# SCH_Pico-Greenhouse-PCB_2026-05-22.net
KiCad netlist of a schematic drawn in EasyEDA
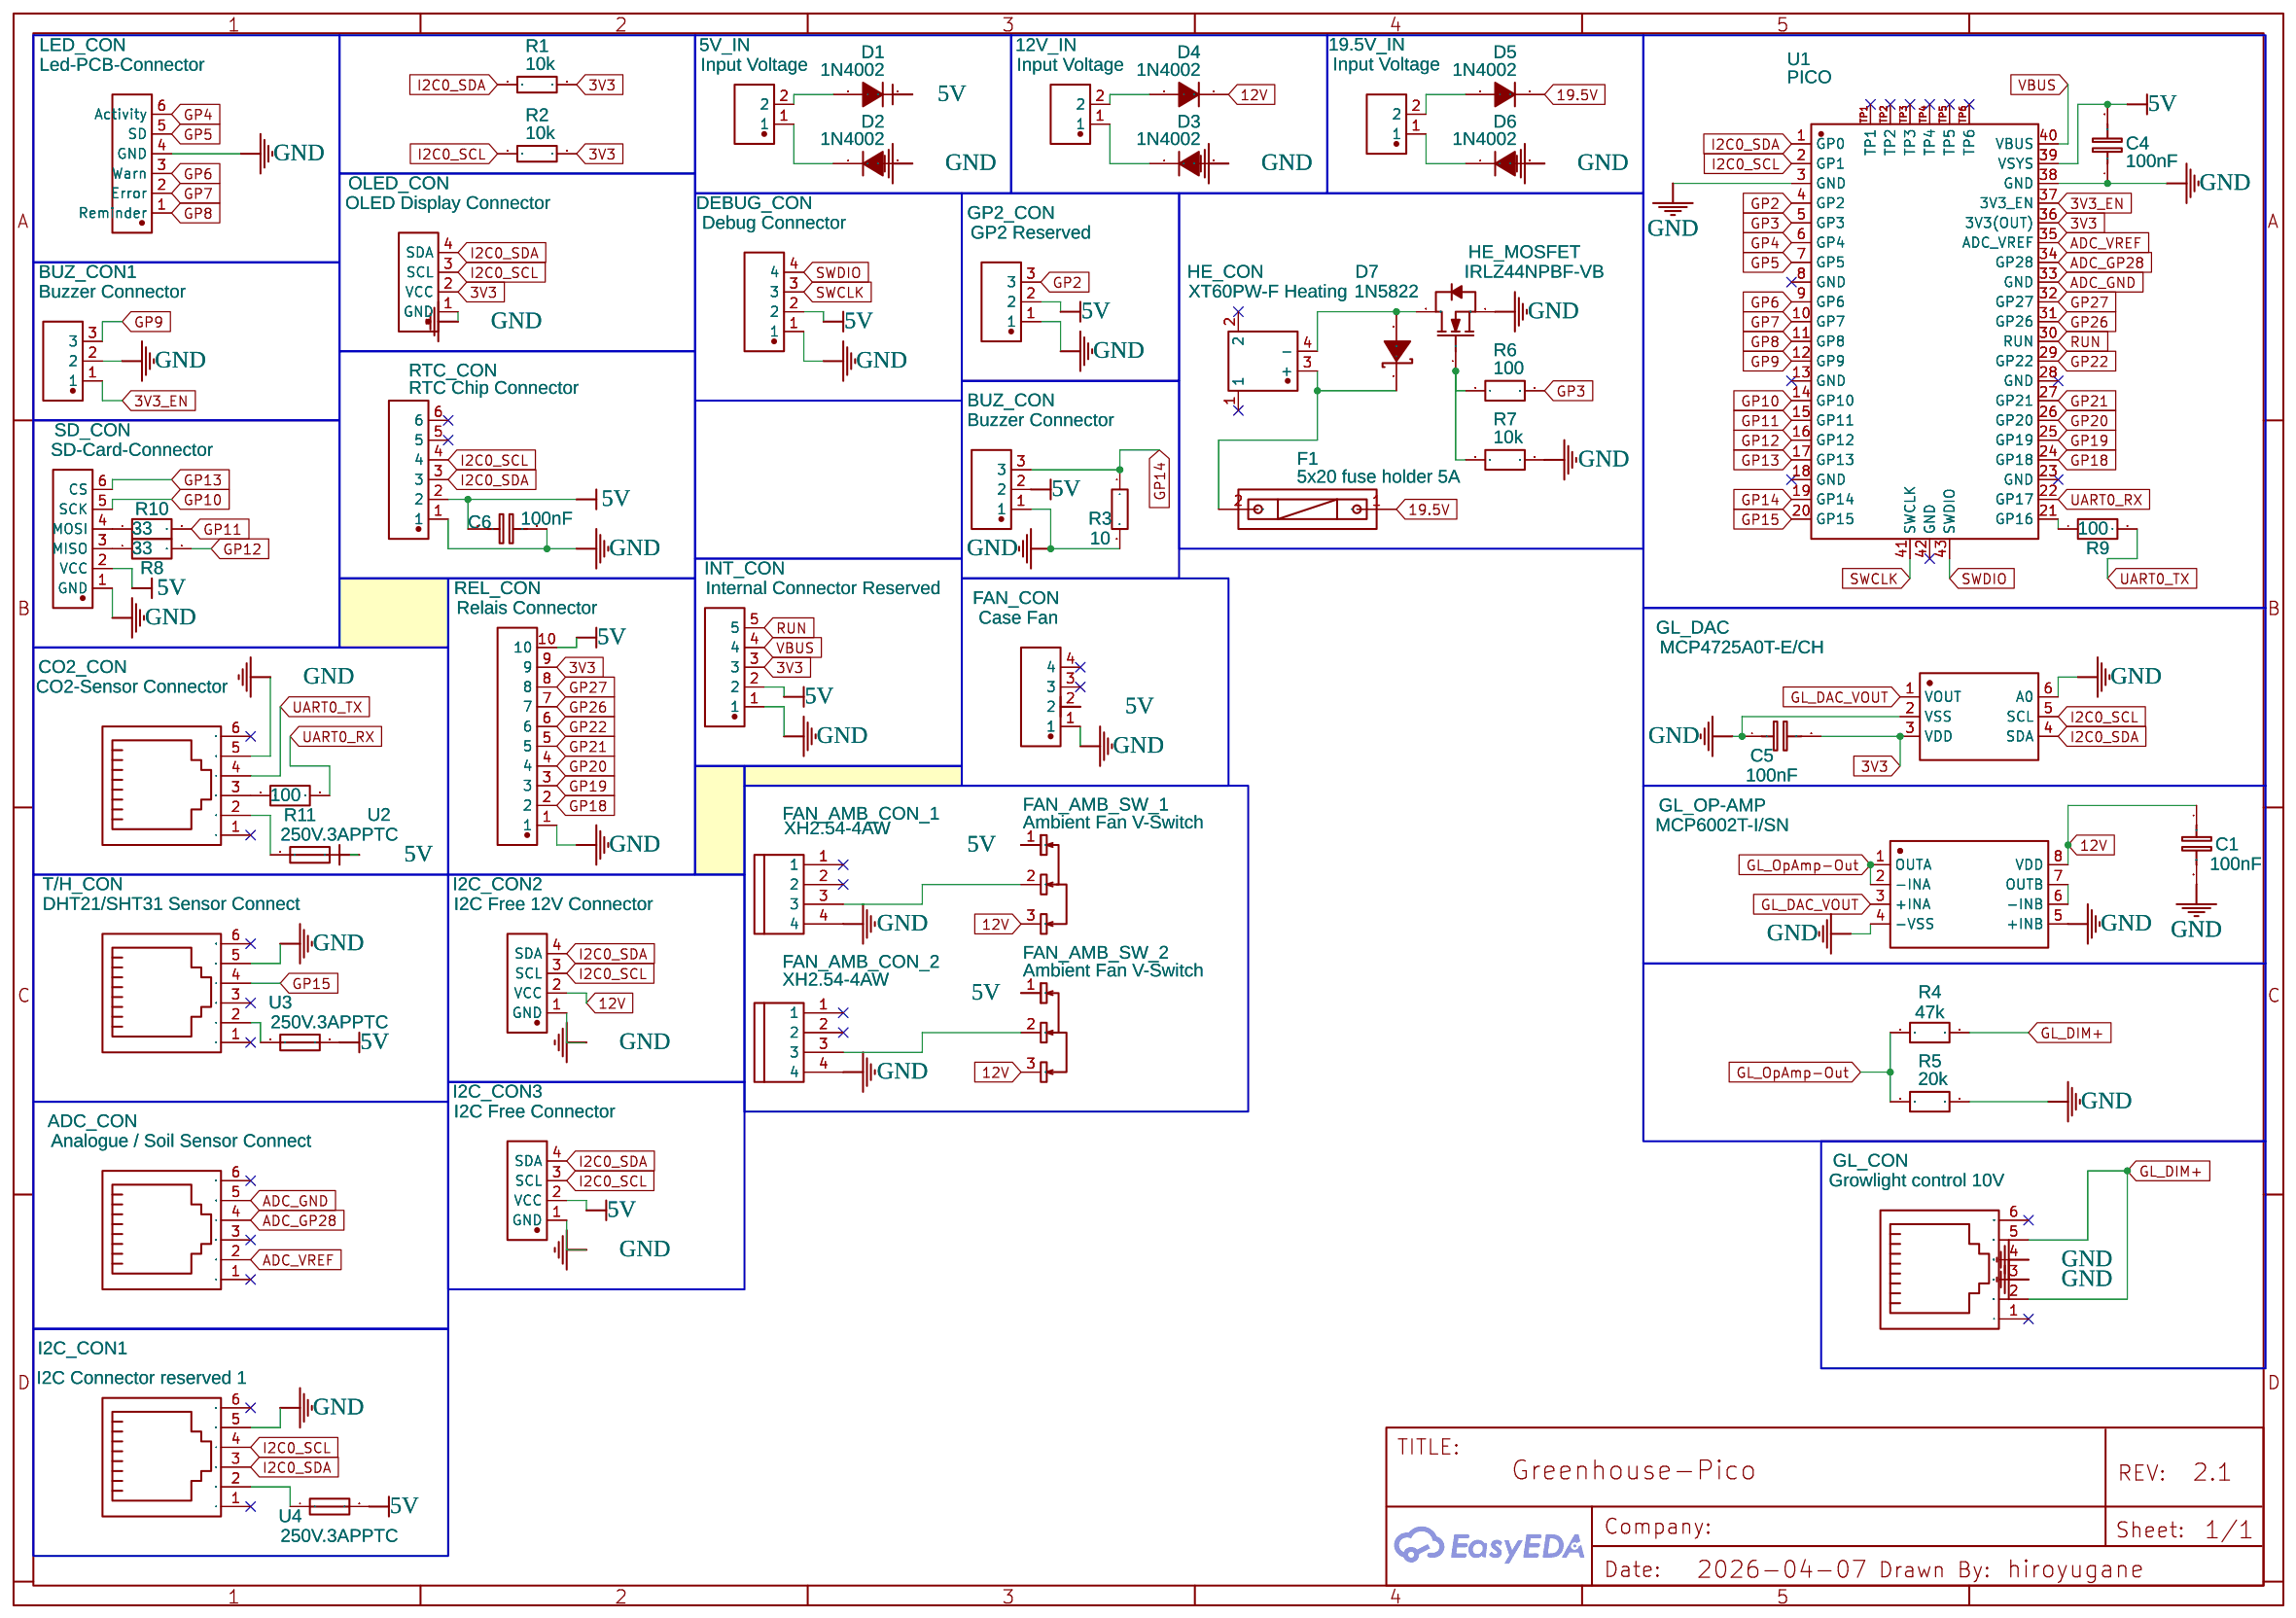
[diagram p0: schematic sheet]

(export (version "E")
  (design (tool "Eeschema 10.0.6"))
  (components
    (comp (ref "5V_IN")
      (value "Input Voltage")
      (fields (field (name "Manufacturer Part") "B2B-XH-A-BK(LF)(SN)") (field (name "Manufacturer") "JST"))
      (libsource (lib "") (part "B2B-XH-A-BK(LF)(SN)_1"))
    )
    (comp (ref "12V_IN")
      (value "Input Voltage")
      (fields (field (name "Manufacturer Part") "B2B-XH-A-BK(LF)(SN)") (field (name "Manufacturer") "JST"))
      (libsource (lib "") (part "B2B-XH-A-BK(LF)(SN)"))
    )
    (comp (ref "19.5V_IN")
      (value "Input Voltage")
      (fields
        (field (name "Manufacturer Part") "1935161")
        (field (name "Manufacturer") "Phoenix Contact(菲尼克斯)")
      )
      (libsource (lib "") (part "1935161"))
    )
    (comp (ref "ADC_CON")
      (value "Analogue / Soil Sensor Connect")
      (fields (field (name "Manufacturer Part") "955012661") (field (name "Manufacturer") "MOLEX"))
      (libsource (lib "") (part "95501-2661"))
    )
    (comp (ref "BUZ_CON")
      (value "Buzzer Connector")
      (fields (field (name "Manufacturer Part") "B3B-XH-A-BK(LF)(SN)") (field (name "Manufacturer") "JST"))
      (libsource (lib "") (part "B3B-XH-A-BK(LF)(SN)_1"))
    )
    (comp (ref "BUZ_CON1")
      (value "Buzzer Connector")
      (fields (field (name "Manufacturer Part") "B3B-XH-A-BK(LF)(SN)") (field (name "Manufacturer") "JST"))
      (libsource (lib "") (part "B3B-XH-A-BK(LF)(SN)_1"))
    )
    (comp (ref "C1") (value "100nF") (libsource (lib "") (part "C_0603_EU_3")))
    (comp (ref "C4") (value "100nF") (libsource (lib "") (part "C_0603_EU_1")))
    (comp (ref "C5") (value "100nF") (libsource (lib "") (part "C_0603_EU")))
    (comp (ref "C6") (value "100nF") (libsource (lib "") (part "C_0603_EU_2")))
    (comp (ref "CO2_CON")
      (value "CO2-Sensor Connector")
      (fields (field (name "Manufacturer Part") "955012661") (field (name "Manufacturer") "MOLEX"))
      (libsource (lib "") (part "95501-2661_4"))
    )
    (comp (ref "D1")
      (value "1N4002")
      (fields (field (name "Manufacturer Part") "1N4002-E3/54") (field (name "Manufacturer") "VISHAY(威世)"))
      (libsource (lib "") (part "1N4002-E3/54"))
    )
    (comp (ref "D2")
      (value "1N4002")
      (fields (field (name "Manufacturer Part") "1N4002-E3/54") (field (name "Manufacturer") "VISHAY(威世)"))
      (libsource (lib "") (part "1N4002-E3/54_1"))
    )
    (comp (ref "D3")
      (value "1N4002")
      (fields (field (name "Manufacturer Part") "1N4002-E3/54") (field (name "Manufacturer") "VISHAY(威世)"))
      (libsource (lib "") (part "1N4002-E3/54_1"))
    )
    (comp (ref "D4")
      (value "1N4002")
      (fields (field (name "Manufacturer Part") "1N4002-E3/54") (field (name "Manufacturer") "VISHAY(威世)"))
      (libsource (lib "") (part "1N4002-E3/54"))
    )
    (comp (ref "D5")
      (value "1N4002")
      (fields (field (name "Manufacturer Part") "1N4002-E3/54") (field (name "Manufacturer") "VISHAY(威世)"))
      (libsource (lib "") (part "1N4002-E3/54"))
    )
    (comp (ref "D6")
      (value "1N4002")
      (fields (field (name "Manufacturer Part") "1N4002-E3/54") (field (name "Manufacturer") "VISHAY(威世)"))
      (libsource (lib "") (part "1N4002-E3/54_1"))
    )
    (comp (ref "D7")
      (value "1N5822")
      (fields (field (name "Manufacturer") "MDD(辰达半导体)"))
      (libsource (lib "") (part "1N5822"))
    )
    (comp (ref "DEBUG_CON")
      (value "Debug Connector")
      (fields (field (name "Manufacturer Part") "B4B-XH-A-R(LF)(SN)") (field (name "Manufacturer") "JST"))
      (libsource (lib "") (part "B4B-XH-A-R(LF)(SN)_3"))
    )
    (comp (ref "F1")
      (value "5x20 fuse holder 5A")
      (fields
        (field (name "Manufacturer Part") "5x20 BLX-A型 保险丝支架 XC-7")
        (field (name "Manufacturer") "xcfuse(旭程)")
      )
      (libsource (lib "") (part "5x20 BLX-Atype Fuse holder XC-7"))
    )
    (comp (ref "FAN_AMB_CON_1")
      (value "XH2.54-4AW")
      (fields (field (name "Manufacturer Part") "XH-4AW") (field (name "Manufacturer") "BOOMELE(博穆精密)"))
      (libsource (lib "") (part "XH2.54-4AW"))
    )
    (comp (ref "FAN_AMB_CON_2")
      (value "XH2.54-4AW")
      (fields (field (name "Manufacturer Part") "XH-4AW") (field (name "Manufacturer") "BOOMELE(博穆精密)"))
      (libsource (lib "") (part "XH2.54-4AW"))
    )
    (comp (ref "FAN_AMB_SW_1")
      (value "Ambient Fan V-Switch")
      (fields
        (field (name "Manufacturer Part") "MST-12D18G4 SPDT Slide Switch")
        (field (name "Manufacturer") "SHOU HAN(首韩)")
      )
      (libsource (lib "") (part "MST-12D18G4 SPDT SLIDE SWITCH"))
    )
    (comp (ref "FAN_AMB_SW_2")
      (value "Ambient Fan V-Switch")
      (fields
        (field (name "Manufacturer Part") "MST-12D18G4 SPDT Slide Switch")
        (field (name "Manufacturer") "SHOU HAN(首韩)")
      )
      (libsource (lib "") (part "MST-12D18G4 SPDT SLIDE SWITCH"))
    )
    (comp (ref "FAN_CON")
      (value "Case Fan")
      (fields (field (name "Manufacturer Part") "B4B-XH-A-R(LF)(SN)") (field (name "Manufacturer") "JST"))
      (libsource (lib "") (part "B4B-XH-A-R(LF)(SN)_1"))
    )
    (comp (ref "GL_CON")
      (value "Growlight control 10V")
      (fields (field (name "Manufacturer Part") "955012661") (field (name "Manufacturer") "MOLEX"))
      (libsource (lib "") (part "95501-2661_3"))
    )
    (comp (ref "GL_DAC")
      (value "MCP4725A0T-E/CH")
      (fields (field (name "Manufacturer") "MICROCHIP(美国微芯)"))
      (libsource (lib "") (part "MCP4725A0T-E/CH"))
    )
    (comp (ref "GL_OP-AMP")
      (value "MCP6002T-I/SN")
      (fields (field (name "Manufacturer") "MICROCHIP(美国微芯)"))
      (libsource (lib "") (part "MCP6002T-I/SN"))
    )
    (comp (ref "GP2_CON")
      (value "GP2 Reserved")
      (fields (field (name "Manufacturer Part") "B3B-XH-A-BK(LF)(SN)") (field (name "Manufacturer") "JST"))
      (libsource (lib "") (part "B3B-XH-A-BK(LF)(SN)"))
    )
    (comp (ref "HE_CON")
      (value "XT60PW-F Heating")
      (fields (field (name "Manufacturer Part") "XT60PW-F") (field (name "Manufacturer") "AMASS(艾迈斯)"))
      (libsource (lib "") (part "XT60PW-F_C428722"))
    )
    (comp (ref "HE_MOSFET")
      (value "IRLZ44NPBF-VB")
      (fields (field (name "Manufacturer") "VBsemi(微碧半导体)"))
      (libsource (lib "") (part "IRLZ44NPBF-VB"))
    )
    (comp (ref "I2C_CON1")
      (value "I2C Connector reserved 1")
      (fields (field (name "Manufacturer Part") "955012661") (field (name "Manufacturer") "MOLEX"))
      (libsource (lib "") (part "95501-2661_1"))
    )
    (comp (ref "I2C_CON2")
      (value "I2C Free 12V Connector")
      (fields (field (name "Manufacturer Part") "B4B-XH-A-R(LF)(SN)") (field (name "Manufacturer") "JST"))
      (libsource (lib "") (part "B4B-XH-A-R(LF)(SN)"))
    )
    (comp (ref "I2C_CON3")
      (value "I2C Free Connector")
      (fields (field (name "Manufacturer Part") "B4B-XH-A-R(LF)(SN)") (field (name "Manufacturer") "JST"))
      (libsource (lib "") (part "B4B-XH-A-R(LF)(SN)"))
    )
    (comp (ref "INT_CON")
      (value "Internal Connector Reserved")
      (fields (field (name "Manufacturer Part") "B5B-XH-A-M(LF)(SN)") (field (name "Manufacturer") "JST"))
      (libsource (lib "") (part "B5B-XH-A-M(LF)(SN)"))
    )
    (comp (ref "LED_CON")
      (value "Led-PCB-Connector")
      (fields (field (name "Manufacturer Part") "B6B-EH(LF)(SN)") (field (name "Manufacturer") "JST"))
      (libsource (lib "") (part "B6B-EH(LF)(SN)"))
    )
    (comp (ref "OLED_CON")
      (value "OLED Display Connector")
      (fields (field (name "Manufacturer Part") "B4B-XH-A-R(LF)(SN)") (field (name "Manufacturer") "JST"))
      (libsource (lib "") (part "B4B-XH-A-R(LF)(SN)_2"))
    )
    (comp (ref "R1")
      (value "10k")
      (fields (field (name "Manufacturer") "Made in China"))
      (libsource (lib "") (part "330Ω (331) ±5%_1"))
    )
    (comp (ref "R2")
      (value "10k")
      (fields (field (name "Manufacturer") "Made in China"))
      (libsource (lib "") (part "330Ω (331) ±5%_1"))
    )
    (comp (ref "R3")
      (value "10")
      (fields (field (name "Manufacturer") "Made in China"))
      (libsource (lib "") (part "330Ω (331) ±5%"))
    )
    (comp (ref "R4") (value "47k") (libsource (lib "") (part "R_0603_EU")))
    (comp (ref "R5") (value "20k") (libsource (lib "") (part "R_0603_EU")))
    (comp (ref "R6") (value "100") (libsource (lib "") (part "R_0603_EU")))
    (comp (ref "R7") (value "10k") (libsource (lib "") (part "R_0603_EU_1")))
    (comp (ref "R8") (value "33") (libsource (lib "") (part "R_0603_EU")))
    (comp (ref "R9") (value "100") (libsource (lib "") (part "R_0603_EU")))
    (comp (ref "R10") (value "33") (libsource (lib "") (part "R_0603_EU")))
    (comp (ref "R11") (value "100") (libsource (lib "") (part "R_0603_EU")))
    (comp (ref "REL_CON")
      (value "Relais Connector")
      (fields (field (name "Manufacturer Part") "B10B-EH(LF)(SN)") (field (name "Manufacturer") "JST"))
      (libsource (lib "") (part "B10B-EH(LF)(SN)"))
    )
    (comp (ref "RTC_CON")
      (value "RTC Chip Connector")
      (fields
        (field (name "Manufacturer Part") "ZX-PM2.54-1-6PY")
        (field (name "Manufacturer") "Megastar(兆星)")
      )
      (libsource (lib "") (part "ZX-PM2.54-1-6PY"))
    )
    (comp (ref "SD_CON")
      (value "SD-Card-Connector")
      (fields (field (name "Manufacturer Part") "B6B-EH(LF)(SN)") (field (name "Manufacturer") "JST"))
      (libsource (lib "") (part "B6B-EH(LF)(SN)_1"))
    )
    (comp (ref "T/H_CON")
      (value "DHT21/SHT31 Sensor Connect")
      (fields (field (name "Manufacturer Part") "955012661") (field (name "Manufacturer") "MOLEX"))
      (libsource (lib "") (part "95501-2661_2"))
    )
    (comp (ref "U1")
      (value "PICO")
      (fields (field (name "Manufacturer") "Raspberry Pi(树莓派)"))
      (libsource (lib "") (part "PICO"))
    )
    (comp (ref "U2")
      (value "250V.3APPTC")
      (fields (field (name "Manufacturer Part") "30V3APPTC"))
      (libsource (lib "") (part "30V3APPTC"))
    )
    (comp (ref "U3")
      (value "250V.3APPTC")
      (fields (field (name "Manufacturer Part") "30V3APPTC"))
      (libsource (lib "") (part "30V3APPTC"))
    )
    (comp (ref "U4")
      (value "250V.3APPTC")
      (fields (field (name "Manufacturer Part") "30V3APPTC"))
      (libsource (lib "") (part "30V3APPTC"))
    )
  )
  (nets
    (net (code "1") (name "3V3") (class "Default")
      (node (ref "C5") (pin "2") (pinfunction "2_2") (pintype "unspecified"))
      (node (ref "GL_DAC") (pin "3") (pinfunction "VDD_3") (pintype "unspecified"))
      (node (ref "INT_CON") (pin "3") (pinfunction "3_3") (pintype "unspecified"))
      (node (ref "OLED_CON") (pin "2") (pinfunction "VCC_2") (pintype "unspecified"))
      (node (ref "R1") (pin "2") (pinfunction "2_2") (pintype "unspecified"))
      (node (ref "R2") (pin "2") (pinfunction "2_2") (pintype "unspecified"))
      (node (ref "REL_CON") (pin "9") (pinfunction "9_9") (pintype "unspecified"))
      (node (ref "U1") (pin "36") (pinfunction "3V3(OUT)_36") (pintype "unspecified"))
    )
    (net (code "2") (name "3V3_EN") (class "Default")
      (node (ref "BUZ_CON1") (pin "1") (pinfunction "1_1") (pintype "unspecified"))
      (node (ref "U1") (pin "37") (pinfunction "3V3_EN_37") (pintype "unspecified"))
    )
    (net (code "3") (name "5V") (class "Default")
      (node (ref "BUZ_CON") (pin "2") (pinfunction "2_2") (pintype "unspecified"))
      (node (ref "C4") (pin "2") (pinfunction "2_2") (pintype "unspecified"))
      (node (ref "C6") (pin "1") (pinfunction "1_1") (pintype "unspecified"))
      (node (ref "D1") (pin "1") (pinfunction "C_1") (pintype "unspecified"))
      (node (ref "DEBUG_CON") (pin "2") (pinfunction "2_2") (pintype "unspecified"))
      (node (ref "FAN_AMB_SW_1") (pin "1") (pinfunction "1_1") (pintype "unspecified"))
      (node (ref "FAN_AMB_SW_2") (pin "1") (pinfunction "1_1") (pintype "unspecified"))
      (node (ref "FAN_CON") (pin "2") (pinfunction "2_2") (pintype "unspecified"))
      (node (ref "GP2_CON") (pin "2") (pinfunction "2_2") (pintype "unspecified"))
      (node (ref "I2C_CON3") (pin "2") (pinfunction "VCC_2") (pintype "unspecified"))
      (node (ref "INT_CON") (pin "2") (pinfunction "2_2") (pintype "unspecified"))
      (node (ref "REL_CON") (pin "10") (pinfunction "10_10") (pintype "unspecified"))
      (node (ref "RTC_CON") (pin "2") (pinfunction "2_2") (pintype "unspecified"))
      (node (ref "SD_CON") (pin "2") (pinfunction "VCC_2") (pintype "unspecified"))
      (node (ref "U1") (pin "39") (pinfunction "VSYS_39") (pintype "unspecified"))
      (node (ref "U2") (pin "2") (pinfunction "2_2") (pintype "unspecified"))
      (node (ref "U3") (pin "2") (pinfunction "2_2") (pintype "unspecified"))
      (node (ref "U4") (pin "2") (pinfunction "2_2") (pintype "unspecified"))
    )
    (net (code "4") (name "12V") (class "Default")
      (node (ref "C1") (pin "1") (pinfunction "1_1") (pintype "unspecified"))
      (node (ref "D4") (pin "1") (pinfunction "C_1") (pintype "unspecified"))
      (node (ref "FAN_AMB_SW_1") (pin "3") (pinfunction "3_3") (pintype "unspecified"))
      (node (ref "FAN_AMB_SW_2") (pin "3") (pinfunction "3_3") (pintype "unspecified"))
      (node (ref "GL_OP-AMP") (pin "8") (pinfunction "VDD_8") (pintype "unspecified"))
      (node (ref "I2C_CON2") (pin "2") (pinfunction "VCC_2") (pintype "unspecified"))
    )
    (net (code "5") (name "19.5V") (class "Default")
      (node (ref "D5") (pin "1") (pinfunction "C_1") (pintype "unspecified"))
      (node (ref "F1") (pin "1") (pinfunction "1_1") (pintype "unspecified"))
    )
    (net (code "6") (name "ADC_GND") (class "Default")
      (node (ref "ADC_CON") (pin "5") (pinfunction "5_5") (pintype "unspecified"))
      (node (ref "U1") (pin "33") (pinfunction "GND_33") (pintype "unspecified"))
    )
    (net (code "7") (name "ADC_GP28") (class "Default")
      (node (ref "ADC_CON") (pin "4") (pinfunction "4_4") (pintype "unspecified"))
      (node (ref "U1") (pin "34") (pinfunction "GP28_34") (pintype "unspecified"))
    )
    (net (code "8") (name "ADC_VREF") (class "Default")
      (node (ref "ADC_CON") (pin "2") (pinfunction "2_2") (pintype "unspecified"))
      (node (ref "U1") (pin "35") (pinfunction "ADC_VREF_35") (pintype "unspecified"))
    )
    (net (code "9") (name "GL_DAC_VOUT") (class "Default")
      (node (ref "GL_DAC") (pin "1") (pinfunction "VOUT_1") (pintype "unspecified"))
      (node (ref "GL_OP-AMP") (pin "3") (pinfunction "+INA_3") (pintype "unspecified"))
    )
    (net (code "10") (name "GL_DIM+") (class "Default")
      (node (ref "GL_CON") (pin "2") (pinfunction "GL+_2") (pintype "unspecified"))
      (node (ref "GL_CON") (pin "5") (pinfunction "GL+_5") (pintype "unspecified"))
      (node (ref "R4") (pin "2") (pinfunction "2_2") (pintype "unspecified"))
    )
    (net (code "11") (name "GL_OpAmp-Out") (class "Default")
      (node (ref "GL_OP-AMP") (pin "1") (pinfunction "OUTA_1") (pintype "unspecified"))
      (node (ref "GL_OP-AMP") (pin "2") (pinfunction "-INA_2") (pintype "unspecified"))
      (node (ref "R4") (pin "1") (pinfunction "1_1") (pintype "unspecified"))
      (node (ref "R5") (pin "1") (pinfunction "1_1") (pintype "unspecified"))
    )
    (net (code "12") (name "GND") (class "Default")
      (node (ref "BUZ_CON") (pin "1") (pinfunction "1_1") (pintype "unspecified"))
      (node (ref "BUZ_CON1") (pin "2") (pinfunction "2_2") (pintype "unspecified"))
      (node (ref "C1") (pin "2") (pinfunction "2_2") (pintype "unspecified"))
      (node (ref "C4") (pin "1") (pinfunction "1_1") (pintype "unspecified"))
      (node (ref "C5") (pin "1") (pinfunction "1_1") (pintype "unspecified"))
      (node (ref "C6") (pin "2") (pinfunction "2_2") (pintype "unspecified"))
      (node (ref "CO2_CON") (pin "5") (pinfunction "5_5") (pintype "unspecified"))
      (node (ref "D2") (pin "2") (pinfunction "A_2") (pintype "unspecified"))
      (node (ref "D3") (pin "2") (pinfunction "A_2") (pintype "unspecified"))
      (node (ref "D6") (pin "2") (pinfunction "A_2") (pintype "unspecified"))
      (node (ref "DEBUG_CON") (pin "1") (pinfunction "1_1") (pintype "unspecified"))
      (node (ref "FAN_AMB_CON_1") (pin "4") (pinfunction "4_4") (pintype "unspecified"))
      (node (ref "FAN_AMB_CON_2") (pin "4") (pinfunction "4_4") (pintype "unspecified"))
      (node (ref "FAN_CON") (pin "1") (pinfunction "1_1") (pintype "unspecified"))
      (node (ref "GL_CON") (pin "3") (pinfunction "GL-_3") (pintype "unspecified"))
      (node (ref "GL_CON") (pin "4") (pinfunction "GL-_4") (pintype "unspecified"))
      (node (ref "GL_DAC") (pin "2") (pinfunction "VSS_2") (pintype "unspecified"))
      (node (ref "GL_DAC") (pin "6") (pinfunction "A0_6") (pintype "unspecified"))
      (node (ref "GL_OP-AMP") (pin "4") (pinfunction "-VSS_4") (pintype "unspecified"))
      (node (ref "GL_OP-AMP") (pin "5") (pinfunction "+INB_5") (pintype "unspecified"))
      (node (ref "GP2_CON") (pin "1") (pinfunction "1_1") (pintype "unspecified"))
      (node (ref "HE_MOSFET") (pin "3") (pinfunction "S_3") (pintype "unspecified"))
      (node (ref "I2C_CON1") (pin "5") (pinfunction "5_5") (pintype "unspecified"))
      (node (ref "I2C_CON2") (pin "1") (pinfunction "GND_1") (pintype "unspecified"))
      (node (ref "I2C_CON3") (pin "1") (pinfunction "GND_1") (pintype "unspecified"))
      (node (ref "INT_CON") (pin "1") (pinfunction "1_1") (pintype "unspecified"))
      (node (ref "LED_CON") (pin "4") (pinfunction "GND_4") (pintype "unspecified"))
      (node (ref "OLED_CON") (pin "1") (pinfunction "GND_1") (pintype "unspecified"))
      (node (ref "R3") (pin "2") (pinfunction "2_2") (pintype "unspecified"))
      (node (ref "R5") (pin "2") (pinfunction "2_2") (pintype "unspecified"))
      (node (ref "R7") (pin "1") (pinfunction "1_1") (pintype "unspecified"))
      (node (ref "REL_CON") (pin "1") (pinfunction "1_1") (pintype "unspecified"))
      (node (ref "RTC_CON") (pin "1") (pinfunction "1_1") (pintype "unspecified"))
      (node (ref "SD_CON") (pin "1") (pinfunction "GND_1") (pintype "unspecified"))
      (node (ref "T/H_CON") (pin "5") (pinfunction "5_5") (pintype "unspecified"))
      (node (ref "U1") (pin "3") (pinfunction "GND_3") (pintype "unspecified"))
      (node (ref "U1") (pin "38") (pinfunction "GND_38") (pintype "unspecified"))
    )
    (net (code "13") (name "GP2") (class "Default")
      (node (ref "GP2_CON") (pin "3") (pinfunction "3_3") (pintype "unspecified"))
      (node (ref "U1") (pin "4") (pinfunction "GP2_4") (pintype "unspecified"))
    )
    (net (code "14") (name "GP3") (class "Default")
      (node (ref "R6") (pin "2") (pinfunction "2_2") (pintype "unspecified"))
      (node (ref "U1") (pin "5") (pinfunction "GP3_5") (pintype "unspecified"))
    )
    (net (code "15") (name "GP4") (class "Default")
      (node (ref "LED_CON") (pin "6") (pinfunction "Activity_6") (pintype "unspecified"))
      (node (ref "U1") (pin "6") (pinfunction "GP4_6") (pintype "unspecified"))
    )
    (net (code "16") (name "GP5") (class "Default")
      (node (ref "LED_CON") (pin "5") (pinfunction "SD_5") (pintype "unspecified"))
      (node (ref "U1") (pin "7") (pinfunction "GP5_7") (pintype "unspecified"))
    )
    (net (code "17") (name "GP6") (class "Default")
      (node (ref "LED_CON") (pin "3") (pinfunction "Warn_3") (pintype "unspecified"))
      (node (ref "U1") (pin "9") (pinfunction "GP6_9") (pintype "unspecified"))
    )
    (net (code "18") (name "GP7") (class "Default")
      (node (ref "LED_CON") (pin "2") (pinfunction "Error_2") (pintype "unspecified"))
      (node (ref "U1") (pin "10") (pinfunction "GP7_10") (pintype "unspecified"))
    )
    (net (code "19") (name "GP8") (class "Default")
      (node (ref "LED_CON") (pin "1") (pinfunction "Reminder_1") (pintype "unspecified"))
      (node (ref "U1") (pin "11") (pinfunction "GP8_11") (pintype "unspecified"))
    )
    (net (code "20") (name "GP9") (class "Default")
      (node (ref "BUZ_CON1") (pin "3") (pinfunction "3_3") (pintype "unspecified"))
      (node (ref "U1") (pin "12") (pinfunction "GP9_12") (pintype "unspecified"))
    )
    (net (code "21") (name "GP10") (class "Default")
      (node (ref "SD_CON") (pin "5") (pinfunction "SCK_5") (pintype "unspecified"))
      (node (ref "U1") (pin "14") (pinfunction "GP10_14") (pintype "unspecified"))
    )
    (net (code "22") (name "GP11") (class "Default")
      (node (ref "R10") (pin "2") (pinfunction "2_2") (pintype "unspecified"))
      (node (ref "U1") (pin "15") (pinfunction "GP11_15") (pintype "unspecified"))
    )
    (net (code "23") (name "GP12") (class "Default")
      (node (ref "R8") (pin "2") (pinfunction "2_2") (pintype "unspecified"))
      (node (ref "U1") (pin "16") (pinfunction "GP12_16") (pintype "unspecified"))
    )
    (net (code "24") (name "GP13") (class "Default")
      (node (ref "SD_CON") (pin "6") (pinfunction "CS_6") (pintype "unspecified"))
      (node (ref "U1") (pin "17") (pinfunction "GP13_17") (pintype "unspecified"))
    )
    (net (code "25") (name "GP14") (class "Default")
      (node (ref "BUZ_CON") (pin "3") (pinfunction "3_3") (pintype "unspecified"))
      (node (ref "R3") (pin "1") (pinfunction "1_1") (pintype "unspecified"))
      (node (ref "U1") (pin "19") (pinfunction "GP14_19") (pintype "unspecified"))
    )
    (net (code "26") (name "GP15") (class "Default")
      (node (ref "T/H_CON") (pin "4") (pinfunction "4_4") (pintype "unspecified"))
      (node (ref "U1") (pin "20") (pinfunction "GP15_20") (pintype "unspecified"))
    )
    (net (code "27") (name "GP18") (class "Default")
      (node (ref "REL_CON") (pin "2") (pinfunction "2_2") (pintype "unspecified"))
      (node (ref "U1") (pin "24") (pinfunction "GP18_24") (pintype "unspecified"))
    )
    (net (code "28") (name "GP19") (class "Default")
      (node (ref "REL_CON") (pin "3") (pinfunction "3_3") (pintype "unspecified"))
      (node (ref "U1") (pin "25") (pinfunction "GP19_25") (pintype "unspecified"))
    )
    (net (code "29") (name "GP20") (class "Default")
      (node (ref "REL_CON") (pin "4") (pinfunction "4_4") (pintype "unspecified"))
      (node (ref "U1") (pin "26") (pinfunction "GP20_26") (pintype "unspecified"))
    )
    (net (code "30") (name "GP21") (class "Default")
      (node (ref "REL_CON") (pin "5") (pinfunction "5_5") (pintype "unspecified"))
      (node (ref "U1") (pin "27") (pinfunction "GP21_27") (pintype "unspecified"))
    )
    (net (code "31") (name "GP22") (class "Default")
      (node (ref "REL_CON") (pin "6") (pinfunction "6_6") (pintype "unspecified"))
      (node (ref "U1") (pin "29") (pinfunction "GP22_29") (pintype "unspecified"))
    )
    (net (code "32") (name "GP26") (class "Default")
      (node (ref "REL_CON") (pin "7") (pinfunction "7_7") (pintype "unspecified"))
      (node (ref "U1") (pin "31") (pinfunction "GP26_31") (pintype "unspecified"))
    )
    (net (code "33") (name "GP27") (class "Default")
      (node (ref "REL_CON") (pin "8") (pinfunction "8_8") (pintype "unspecified"))
      (node (ref "U1") (pin "32") (pinfunction "GP27_32") (pintype "unspecified"))
    )
    (net (code "34") (name "I2C0_SCL") (class "Default")
      (node (ref "GL_DAC") (pin "5") (pinfunction "SCL_5") (pintype "unspecified"))
      (node (ref "I2C_CON1") (pin "4") (pinfunction "4_4") (pintype "unspecified"))
      (node (ref "I2C_CON2") (pin "3") (pinfunction "SCL_3") (pintype "unspecified"))
      (node (ref "I2C_CON3") (pin "3") (pinfunction "SCL_3") (pintype "unspecified"))
      (node (ref "OLED_CON") (pin "3") (pinfunction "SCL_3") (pintype "unspecified"))
      (node (ref "R2") (pin "1") (pinfunction "1_1") (pintype "unspecified"))
      (node (ref "RTC_CON") (pin "4") (pinfunction "4_4") (pintype "unspecified"))
      (node (ref "U1") (pin "2") (pinfunction "GP1_2") (pintype "unspecified"))
    )
    (net (code "35") (name "I2C0_SDA") (class "Default")
      (node (ref "GL_DAC") (pin "4") (pinfunction "SDA_4") (pintype "unspecified"))
      (node (ref "I2C_CON1") (pin "3") (pinfunction "3_3") (pintype "unspecified"))
      (node (ref "I2C_CON2") (pin "4") (pinfunction "SDA_4") (pintype "unspecified"))
      (node (ref "I2C_CON3") (pin "4") (pinfunction "SDA_4") (pintype "unspecified"))
      (node (ref "OLED_CON") (pin "4") (pinfunction "SDA_4") (pintype "unspecified"))
      (node (ref "R1") (pin "1") (pinfunction "1_1") (pintype "unspecified"))
      (node (ref "RTC_CON") (pin "3") (pinfunction "3_3") (pintype "unspecified"))
      (node (ref "U1") (pin "1") (pinfunction "GP0_1") (pintype "unspecified"))
    )
    (net (code "36") (name "Net-(CO2_CON-Pad2)") (class "Default")
      (node (ref "CO2_CON") (pin "2") (pinfunction "2_2") (pintype "unspecified"))
      (node (ref "U2") (pin "1") (pinfunction "1_1") (pintype "unspecified"))
    )
    (net (code "37") (name "Net-(CO2_CON-Pad3)") (class "Default")
      (node (ref "CO2_CON") (pin "3") (pinfunction "3_3") (pintype "unspecified"))
      (node (ref "R11") (pin "1") (pinfunction "1_1") (pintype "unspecified"))
    )
    (net (code "38") (name "Net-(D1-A)") (class "Default")
      (node (ref "5V_IN") (pin "2") (pinfunction "2_2") (pintype "unspecified"))
      (node (ref "D1") (pin "2") (pinfunction "A_2") (pintype "unspecified"))
    )
    (net (code "39") (name "Net-(D2-C)") (class "Default")
      (node (ref "5V_IN") (pin "1") (pinfunction "1_1") (pintype "unspecified"))
      (node (ref "D2") (pin "1") (pinfunction "C_1") (pintype "unspecified"))
    )
    (net (code "40") (name "Net-(D3-C)") (class "Default")
      (node (ref "12V_IN") (pin "1") (pinfunction "1_1") (pintype "unspecified"))
      (node (ref "D3") (pin "1") (pinfunction "C_1") (pintype "unspecified"))
    )
    (net (code "41") (name "Net-(D4-A)") (class "Default")
      (node (ref "12V_IN") (pin "2") (pinfunction "2_2") (pintype "unspecified"))
      (node (ref "D4") (pin "2") (pinfunction "A_2") (pintype "unspecified"))
    )
    (net (code "42") (name "Net-(D5-A)") (class "Default")
      (node (ref "19.5V_IN") (pin "2") (pinfunction "2_2") (pintype "unspecified"))
      (node (ref "D5") (pin "2") (pinfunction "A_2") (pintype "unspecified"))
    )
    (net (code "43") (name "Net-(D6-C)") (class "Default")
      (node (ref "19.5V_IN") (pin "1") (pinfunction "1_1") (pintype "unspecified"))
      (node (ref "D6") (pin "1") (pinfunction "C_1") (pintype "unspecified"))
    )
    (net (code "44") (name "Net-(D7-A)") (class "Default")
      (node (ref "D7") (pin "1") (pinfunction "A_1") (pintype "unspecified"))
      (node (ref "HE_CON") (pin "4") (pinfunction "-_4") (pintype "unspecified"))
      (node (ref "HE_MOSFET") (pin "2") (pinfunction "D_2") (pintype "unspecified"))
    )
    (net (code "45") (name "Net-(D7-K)") (class "Default")
      (node (ref "D7") (pin "2") (pinfunction "K_2") (pintype "unspecified"))
      (node (ref "F1") (pin "2") (pinfunction "2_2") (pintype "unspecified"))
      (node (ref "HE_CON") (pin "3") (pinfunction "+_3") (pintype "unspecified"))
    )
    (net (code "46") (name "Net-(FAN_AMB_CON_1-Pad3)") (class "Default")
      (node (ref "FAN_AMB_CON_1") (pin "3") (pinfunction "3_3") (pintype "unspecified"))
      (node (ref "FAN_AMB_SW_1") (pin "2") (pinfunction "2_2") (pintype "unspecified"))
    )
    (net (code "47") (name "Net-(FAN_AMB_CON_2-Pad3)") (class "Default")
      (node (ref "FAN_AMB_CON_2") (pin "3") (pinfunction "3_3") (pintype "unspecified"))
      (node (ref "FAN_AMB_SW_2") (pin "2") (pinfunction "2_2") (pintype "unspecified"))
    )
    (net (code "48") (name "Net-(GL_OP-AMP--INB)") (class "Default")
      (node (ref "GL_OP-AMP") (pin "6") (pinfunction "-INB_6") (pintype "unspecified"))
      (node (ref "GL_OP-AMP") (pin "7") (pinfunction "OUTB_7") (pintype "unspecified"))
    )
    (net (code "49") (name "Net-(HE_MOSFET-G)") (class "Default")
      (node (ref "HE_MOSFET") (pin "1") (pinfunction "G_1") (pintype "unspecified"))
      (node (ref "R6") (pin "1") (pinfunction "1_1") (pintype "unspecified"))
      (node (ref "R7") (pin "2") (pinfunction "2_2") (pintype "unspecified"))
    )
    (net (code "50") (name "Net-(I2C_CON1-Pad2)") (class "Default")
      (node (ref "I2C_CON1") (pin "2") (pinfunction "2_2") (pintype "unspecified"))
      (node (ref "U4") (pin "1") (pinfunction "1_1") (pintype "unspecified"))
    )
    (net (code "51") (name "Net-(SD_CON-MISO)") (class "Default")
      (node (ref "R8") (pin "1") (pinfunction "1_1") (pintype "unspecified"))
      (node (ref "SD_CON") (pin "3") (pinfunction "MISO_3") (pintype "unspecified"))
    )
    (net (code "52") (name "Net-(SD_CON-MOSI)") (class "Default")
      (node (ref "R10") (pin "1") (pinfunction "1_1") (pintype "unspecified"))
      (node (ref "SD_CON") (pin "4") (pinfunction "MOSI_4") (pintype "unspecified"))
    )
    (net (code "53") (name "Net-(T/H_CON-Pad2)") (class "Default")
      (node (ref "T/H_CON") (pin "2") (pinfunction "2_2") (pintype "unspecified"))
      (node (ref "U3") (pin "1") (pinfunction "1_1") (pintype "unspecified"))
    )
    (net (code "54") (name "Net-(U1-GP16)") (class "Default")
      (node (ref "R9") (pin "1") (pinfunction "1_1") (pintype "unspecified"))
      (node (ref "U1") (pin "21") (pinfunction "GP16_21") (pintype "unspecified"))
    )
    (net (code "55") (name "RUN") (class "Default")
      (node (ref "INT_CON") (pin "5") (pinfunction "5_5") (pintype "unspecified"))
      (node (ref "U1") (pin "30") (pinfunction "RUN_30") (pintype "unspecified"))
    )
    (net (code "56") (name "SWCLK") (class "Default")
      (node (ref "DEBUG_CON") (pin "3") (pinfunction "3_3") (pintype "unspecified"))
      (node (ref "U1") (pin "41") (pinfunction "SWCLK_41") (pintype "unspecified"))
    )
    (net (code "57") (name "SWDIO") (class "Default")
      (node (ref "DEBUG_CON") (pin "4") (pinfunction "4_4") (pintype "unspecified"))
      (node (ref "U1") (pin "43") (pinfunction "SWDIO_43") (pintype "unspecified"))
    )
    (net (code "58") (name "UART0_RX") (class "Default")
      (node (ref "R11") (pin "2") (pinfunction "2_2") (pintype "unspecified"))
      (node (ref "U1") (pin "22") (pinfunction "GP17_22") (pintype "unspecified"))
    )
    (net (code "59") (name "UART0_TX") (class "Default")
      (node (ref "CO2_CON") (pin "4") (pinfunction "4_4") (pintype "unspecified"))
      (node (ref "R9") (pin "2") (pinfunction "2_2") (pintype "unspecified"))
    )
    (net (code "60") (name "VBUS") (class "Default")
      (node (ref "INT_CON") (pin "4") (pinfunction "4_4") (pintype "unspecified"))
      (node (ref "U1") (pin "40") (pinfunction "VBUS_40") (pintype "unspecified"))
    )
    (net (code "61") (name "unconnected-(ADC_CON-Pad1)") (class "Default")
      (node (ref "ADC_CON") (pin "1") (pinfunction "1_1") (pintype "unspecified+no_connect"))
    )
    (net (code "62") (name "unconnected-(ADC_CON-Pad3)") (class "Default")
      (node (ref "ADC_CON") (pin "3") (pinfunction "3_3") (pintype "unspecified+no_connect"))
    )
    (net (code "63") (name "unconnected-(ADC_CON-Pad6)") (class "Default")
      (node (ref "ADC_CON") (pin "6") (pinfunction "6_6") (pintype "unspecified+no_connect"))
    )
    (net (code "64") (name "unconnected-(CO2_CON-Pad1)") (class "Default")
      (node (ref "CO2_CON") (pin "1") (pinfunction "1_1") (pintype "unspecified+no_connect"))
    )
    (net (code "65") (name "unconnected-(CO2_CON-Pad6)") (class "Default")
      (node (ref "CO2_CON") (pin "6") (pinfunction "6_6") (pintype "unspecified+no_connect"))
    )
    (net (code "66") (name "unconnected-(FAN_AMB_CON_1-Pad1)") (class "Default")
      (node (ref "FAN_AMB_CON_1") (pin "1") (pinfunction "1_1") (pintype "unspecified+no_connect"))
    )
    (net (code "67") (name "unconnected-(FAN_AMB_CON_1-Pad2)") (class "Default")
      (node (ref "FAN_AMB_CON_1") (pin "2") (pinfunction "2_2") (pintype "unspecified+no_connect"))
    )
    (net (code "68") (name "unconnected-(FAN_AMB_CON_2-Pad1)") (class "Default")
      (node (ref "FAN_AMB_CON_2") (pin "1") (pinfunction "1_1") (pintype "unspecified+no_connect"))
    )
    (net (code "69") (name "unconnected-(FAN_AMB_CON_2-Pad2)") (class "Default")
      (node (ref "FAN_AMB_CON_2") (pin "2") (pinfunction "2_2") (pintype "unspecified+no_connect"))
    )
    (net (code "70") (name "unconnected-(FAN_CON-Pad3)") (class "Default")
      (node (ref "FAN_CON") (pin "3") (pinfunction "3_3") (pintype "unspecified+no_connect"))
    )
    (net (code "71") (name "unconnected-(FAN_CON-Pad4)") (class "Default")
      (node (ref "FAN_CON") (pin "4") (pinfunction "4_4") (pintype "unspecified+no_connect"))
    )
    (net (code "72") (name "unconnected-(GL_CON-Pad1)") (class "Default")
      (node (ref "GL_CON") (pin "1") (pinfunction "1_1") (pintype "unspecified+no_connect"))
    )
    (net (code "73") (name "unconnected-(GL_CON-Pad6)") (class "Default")
      (node (ref "GL_CON") (pin "6") (pinfunction "6_6") (pintype "unspecified+no_connect"))
    )
    (net (code "74") (name "unconnected-(HE_CON-Pad1)") (class "Default")
      (node (ref "HE_CON") (pin "1") (pinfunction "1_1") (pintype "unspecified+no_connect"))
    )
    (net (code "75") (name "unconnected-(HE_CON-Pad2)") (class "Default")
      (node (ref "HE_CON") (pin "2") (pinfunction "2_2") (pintype "unspecified+no_connect"))
    )
    (net (code "76") (name "unconnected-(I2C_CON1-Pad1)") (class "Default")
      (node (ref "I2C_CON1") (pin "1") (pinfunction "1_1") (pintype "unspecified+no_connect"))
    )
    (net (code "77") (name "unconnected-(I2C_CON1-Pad6)") (class "Default")
      (node (ref "I2C_CON1") (pin "6") (pinfunction "6_6") (pintype "unspecified+no_connect"))
    )
    (net (code "78") (name "unconnected-(RTC_CON-Pad5)") (class "Default")
      (node (ref "RTC_CON") (pin "5") (pinfunction "5_5") (pintype "unspecified+no_connect"))
    )
    (net (code "79") (name "unconnected-(RTC_CON-Pad6)") (class "Default")
      (node (ref "RTC_CON") (pin "6") (pinfunction "6_6") (pintype "unspecified+no_connect"))
    )
    (net (code "80") (name "unconnected-(T/H_CON-Pad1)") (class "Default")
      (node (ref "T/H_CON") (pin "1") (pinfunction "1_1") (pintype "unspecified+no_connect"))
    )
    (net (code "81") (name "unconnected-(T/H_CON-Pad3)") (class "Default")
      (node (ref "T/H_CON") (pin "3") (pinfunction "3_3") (pintype "unspecified+no_connect"))
    )
    (net (code "82") (name "unconnected-(T/H_CON-Pad6)") (class "Default")
      (node (ref "T/H_CON") (pin "6") (pinfunction "6_6") (pintype "unspecified+no_connect"))
    )
    (net (code "83") (name "unconnected-(U1-GND-Pad8)") (class "Default")
      (node (ref "U1") (pin "8") (pinfunction "GND_8") (pintype "unspecified+no_connect"))
    )
    (net (code "84") (name "unconnected-(U1-GND-Pad13)") (class "Default")
      (node (ref "U1") (pin "13") (pinfunction "GND_13") (pintype "unspecified+no_connect"))
    )
    (net (code "85") (name "unconnected-(U1-GND-Pad18)") (class "Default")
      (node (ref "U1") (pin "18") (pinfunction "GND_18") (pintype "unspecified+no_connect"))
    )
    (net (code "86") (name "unconnected-(U1-GND-Pad23)") (class "Default")
      (node (ref "U1") (pin "23") (pinfunction "GND_23") (pintype "unspecified+no_connect"))
    )
    (net (code "87") (name "unconnected-(U1-GND-Pad28)") (class "Default")
      (node (ref "U1") (pin "28") (pinfunction "GND_28") (pintype "unspecified+no_connect"))
    )
    (net (code "88") (name "unconnected-(U1-GND-Pad42)") (class "Default")
      (node (ref "U1") (pin "42") (pinfunction "GND_42") (pintype "unspecified+no_connect"))
    )
    (net (code "89") (name "unconnected-(U1-PadTP1)") (class "Default")
      (node (ref "U1") (pin "TP1") (pinfunction "TP1_TP1") (pintype "unspecified+no_connect"))
    )
    (net (code "90") (name "unconnected-(U1-PadTP2)") (class "Default")
      (node (ref "U1") (pin "TP2") (pinfunction "TP2_TP2") (pintype "unspecified+no_connect"))
    )
    (net (code "91") (name "unconnected-(U1-PadTP3)") (class "Default")
      (node (ref "U1") (pin "TP3") (pinfunction "TP3_TP3") (pintype "unspecified+no_connect"))
    )
    (net (code "92") (name "unconnected-(U1-PadTP4)") (class "Default")
      (node (ref "U1") (pin "TP4") (pinfunction "TP4_TP4") (pintype "unspecified+no_connect"))
    )
    (net (code "93") (name "unconnected-(U1-PadTP5)") (class "Default")
      (node (ref "U1") (pin "TP5") (pinfunction "TP5_TP5") (pintype "unspecified+no_connect"))
    )
    (net (code "94") (name "unconnected-(U1-PadTP6)") (class "Default")
      (node (ref "U1") (pin "TP6") (pinfunction "TP6_TP6") (pintype "unspecified+no_connect"))
    )
  )
)
